# Rx_Universal_SK.net
KiCad netlist of a schematic drawn in Altium Designer
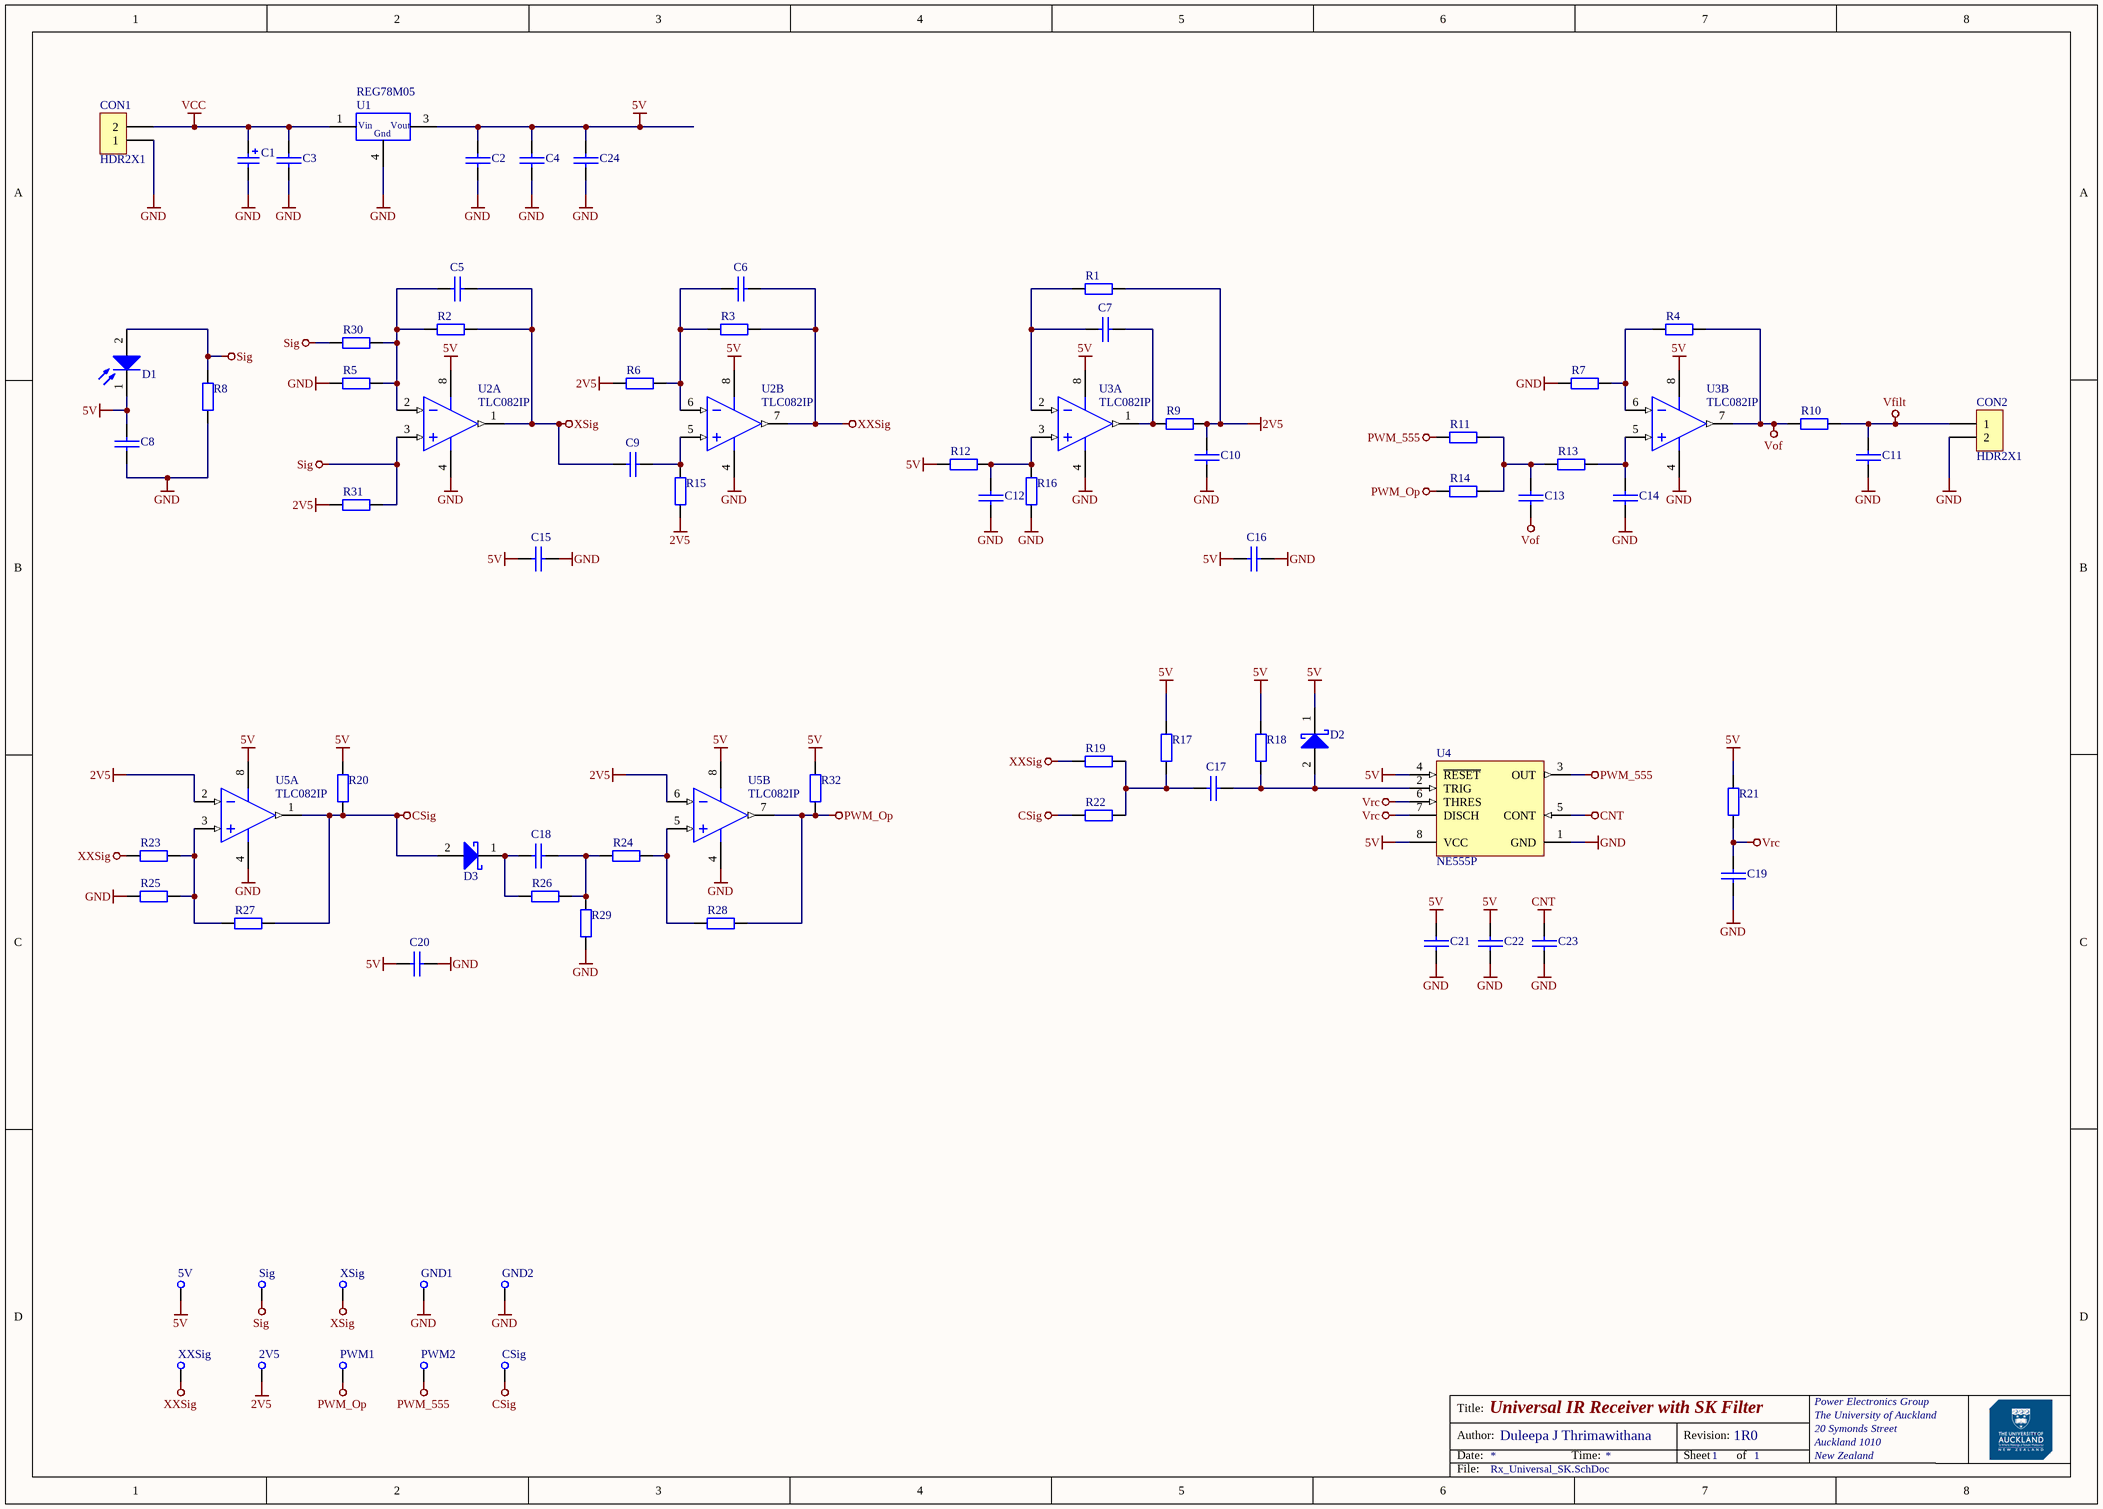
[diagram p0: Rx_Universal_SK.SchDoc]

(export (version "E")
  (design (tool "Eeschema 10.0.6"))
  (components
    (comp (ref "2V5")
      (value "TP TH")
      (footprint "TP_TH_2.5mm")
      (fields (field (name "SOURCE") "UoAPE_Connectors and Mechanical.SchLib"))
      (libsource (lib "ECSE@UoA") (part "TP TH"))
    )
    (comp (ref "5V")
      (value "TP TH")
      (footprint "TP_TH_2.5mm")
      (fields (field (name "SOURCE") "UoAPE_Connectors and Mechanical.SchLib"))
      (libsource (lib "ECSE@UoA") (part "TP TH"))
    )
    (comp (ref "C1") (value "ECAP") (footprint "CR05") (libsource (lib "ECSE@UoA") (part "ECAP")))
    (comp (ref "C2")
      (value "CCAP_TH_5P0")
      (footprint "CCAP_5P0")
      (description "TH ceramic cap with 5mm pitch")
      (libsource (lib "") (part "Symbol_2"))
    )
    (comp (ref "C3")
      (value "CCAP_TH_5P0")
      (footprint "CCAP_5P0")
      (description "TH ceramic cap with 5mm pitch")
      (libsource (lib "") (part "Symbol_2"))
    )
    (comp (ref "C4")
      (value "CCAP_TH_5P0")
      (footprint "CCAP_5P0")
      (description "TH ceramic cap with 5mm pitch")
      (libsource (lib "") (part "Symbol_2"))
    )
    (comp (ref "C5")
      (value "CCAP_TH_5P0")
      (footprint "CCAP_5P0")
      (description "TH ceramic cap with 5mm pitch")
      (libsource (lib "") (part "Symbol_2"))
    )
    (comp (ref "C6")
      (value "CCAP_TH_5P0")
      (footprint "CCAP_5P0")
      (description "TH ceramic cap with 5mm pitch")
      (libsource (lib "") (part "Symbol_2"))
    )
    (comp (ref "C7")
      (value "CCAP_TH_5P0")
      (footprint "CCAP_5P0")
      (description "TH ceramic cap with 5mm pitch")
      (libsource (lib "") (part "Symbol_2"))
    )
    (comp (ref "C8")
      (value "CCAP_TH_5P0")
      (footprint "CCAP_5P0")
      (description "TH ceramic cap with 5mm pitch")
      (libsource (lib "") (part "Symbol_2"))
    )
    (comp (ref "C9")
      (value "CCAP_TH_5P0")
      (footprint "CCAP_5P0")
      (description "TH ceramic cap with 5mm pitch")
      (libsource (lib "") (part "Symbol_2"))
    )
    (comp (ref "C10")
      (value "CCAP_TH_5P0")
      (footprint "CCAP_5P0")
      (description "TH ceramic cap with 5mm pitch")
      (libsource (lib "") (part "Symbol_2"))
    )
    (comp (ref "C11")
      (value "CCAP_TH_5P0")
      (footprint "CCAP_5P0")
      (description "TH ceramic cap with 5mm pitch")
      (libsource (lib "") (part "Symbol_2"))
    )
    (comp (ref "C12")
      (value "CCAP_TH_5P0")
      (footprint "CCAP_5P0")
      (description "TH ceramic cap with 5mm pitch")
      (libsource (lib "") (part "Symbol_2"))
    )
    (comp (ref "C13")
      (value "CCAP_TH_5P0")
      (footprint "CCAP_5P0")
      (description "TH ceramic cap with 5mm pitch")
      (libsource (lib "") (part "Symbol_2"))
    )
    (comp (ref "C14")
      (value "CCAP_TH_5P0")
      (footprint "CCAP_5P0")
      (description "TH ceramic cap with 5mm pitch")
      (libsource (lib "") (part "Symbol_2"))
    )
    (comp (ref "C15")
      (value "CCAP_TH_5P0")
      (footprint "CCAP_5P0")
      (description "TH ceramic cap with 5mm pitch")
      (libsource (lib "") (part "Symbol_2"))
    )
    (comp (ref "C16")
      (value "CCAP_TH_5P0")
      (footprint "CCAP_5P0")
      (description "TH ceramic cap with 5mm pitch")
      (libsource (lib "") (part "Symbol_2"))
    )
    (comp (ref "C17")
      (value "CCAP_TH_5P0")
      (footprint "CCAP_5P0")
      (description "TH ceramic cap with 5mm pitch")
      (libsource (lib "") (part "Symbol_2"))
    )
    (comp (ref "C18")
      (value "CCAP_TH_5P0")
      (footprint "CCAP_5P0")
      (description "TH ceramic cap with 5mm pitch")
      (libsource (lib "") (part "Symbol_2"))
    )
    (comp (ref "C19")
      (value "CCAP_TH_5P0")
      (footprint "CCAP_5P0")
      (description "TH ceramic cap with 5mm pitch")
      (libsource (lib "") (part "Symbol_2"))
    )
    (comp (ref "C20")
      (value "CCAP_TH_5P0")
      (footprint "CCAP_5P0")
      (description "TH ceramic cap with 5mm pitch")
      (libsource (lib "") (part "Symbol_2"))
    )
    (comp (ref "C21")
      (value "CCAP_TH_5P0")
      (footprint "CCAP_5P0")
      (description "TH ceramic cap with 5mm pitch")
      (libsource (lib "") (part "Symbol_2"))
    )
    (comp (ref "C22")
      (value "CCAP_TH_5P0")
      (footprint "CCAP_5P0")
      (description "TH ceramic cap with 5mm pitch")
      (libsource (lib "") (part "Symbol_2"))
    )
    (comp (ref "C23")
      (value "CCAP_TH_5P0")
      (footprint "CCAP_5P0")
      (description "TH ceramic cap with 5mm pitch")
      (libsource (lib "") (part "Symbol_2"))
    )
    (comp (ref "C24")
      (value "CCAP_TH_5P0")
      (footprint "CCAP_5P0")
      (description "TH ceramic cap with 5mm pitch")
      (libsource (lib "") (part "Symbol_2"))
    )
    (comp (ref "CON1")
      (value "HDR2X1")
      (footprint "HDR2X1_2P54")
      (description "Header 2X1")
      (libsource (lib "") (part "HDR2X1_1"))
    )
    (comp (ref "CON2")
      (value "HDR2X1")
      (footprint "HDR2X1_2P54")
      (description "Header 2X1")
      (libsource (lib "ECSE@UoA") (part "HDR2X1"))
    )
    (comp (ref "CSig")
      (value "TP TH")
      (footprint "TP_TH_2.5mm")
      (fields (field (name "SOURCE") "UoAPE_Connectors and Mechanical.SchLib"))
      (libsource (lib "ECSE@UoA") (part "TP TH"))
    )
    (comp (ref "D1")
      (value "PhotoD_TH")
      (footprint "TH_LED")
      (description "Photo diode")
      (libsource (lib "ECSE@UoA") (part "Copy of 8706943c75ba83719d021d2fdc84c58"))
    )
    (comp (ref "D2")
      (value "BAT85,113")
      (footprint "FP-SOD68-MFG")
      (description "Rectifier Diode, Schottky, 1 Phase, 1 Element, 0.2A, 30V V(RRM), Silicon, DO-34")
      (libsource (lib "ECSE@UoA") (part "1d6ec82d83fb6aee721767c19dac4b9"))
    )
    (comp (ref "D3")
      (value "BAT85,113")
      (footprint "FP-SOD68-MFG")
      (description "Rectifier Diode, Schottky, 1 Phase, 1 Element, 0.2A, 30V V(RRM), Silicon, DO-34")
      (libsource (lib "ECSE@UoA") (part "1d6ec82d83fb6aee721767c19dac4b9"))
    )
    (comp (ref "GND1")
      (value "TP TH")
      (footprint "TP_TH_2.5mm")
      (fields (field (name "SOURCE") "UoAPE_Connectors and Mechanical.SchLib"))
      (libsource (lib "ECSE@UoA") (part "TP TH"))
    )
    (comp (ref "GND2")
      (value "TP TH")
      (footprint "TP_TH_2.5mm")
      (fields (field (name "SOURCE") "UoAPE_Connectors and Mechanical.SchLib"))
      (libsource (lib "ECSE@UoA") (part "TP TH"))
    )
    (comp (ref "PWM1")
      (value "TP TH")
      (footprint "TP_TH_2.5mm")
      (fields (field (name "SOURCE") "UoAPE_Connectors and Mechanical.SchLib"))
      (libsource (lib "ECSE@UoA") (part "TP TH"))
    )
    (comp (ref "PWM2")
      (value "TP TH")
      (footprint "TP_TH_2.5mm")
      (fields (field (name "SOURCE") "UoAPE_Connectors and Mechanical.SchLib"))
      (libsource (lib "ECSE@UoA") (part "TP TH"))
    )
    (comp (ref "R1")
      (value "RESAX4")
      (footprint "RAX4")
      (description "Axial Resistor")
      (libsource (lib "") (part "Symbol_1"))
    )
    (comp (ref "R2")
      (value "RESAX4")
      (footprint "RAX4")
      (description "Axial Resistor")
      (libsource (lib "") (part "Symbol_1"))
    )
    (comp (ref "R3")
      (value "RESAX4")
      (footprint "RAX4")
      (description "Axial Resistor")
      (libsource (lib "") (part "Symbol_1"))
    )
    (comp (ref "R4")
      (value "RESAX4")
      (footprint "RAX4")
      (description "Axial Resistor")
      (libsource (lib "") (part "Symbol_1"))
    )
    (comp (ref "R5")
      (value "RESAX4")
      (footprint "RAX4")
      (description "Axial Resistor")
      (libsource (lib "") (part "Symbol_1"))
    )
    (comp (ref "R6")
      (value "RESAX4")
      (footprint "RAX4")
      (description "Axial Resistor")
      (libsource (lib "") (part "Symbol_1"))
    )
    (comp (ref "R7")
      (value "RESAX4")
      (footprint "RAX4")
      (description "Axial Resistor")
      (libsource (lib "") (part "Symbol_1"))
    )
    (comp (ref "R8")
      (value "RESAX4")
      (footprint "RAX4")
      (description "Axial Resistor")
      (libsource (lib "ECSE@UoA") (part "Symbol"))
    )
    (comp (ref "R9")
      (value "RESAX4")
      (footprint "RAX4")
      (description "Axial Resistor")
      (libsource (lib "") (part "Symbol_1"))
    )
    (comp (ref "R10")
      (value "RESAX4")
      (footprint "RAX4")
      (description "Axial Resistor")
      (libsource (lib "") (part "Symbol_1"))
    )
    (comp (ref "R11")
      (value "RESAX4")
      (footprint "RAX4")
      (description "Axial Resistor")
      (libsource (lib "") (part "Symbol_1"))
    )
    (comp (ref "R12")
      (value "RESAX4")
      (footprint "RAX4")
      (description "Axial Resistor")
      (libsource (lib "") (part "Symbol_1"))
    )
    (comp (ref "R13")
      (value "RESAX4")
      (footprint "RAX4")
      (description "Axial Resistor")
      (libsource (lib "") (part "Symbol_1"))
    )
    (comp (ref "R14")
      (value "RESAX4")
      (footprint "RAX4")
      (description "Axial Resistor")
      (libsource (lib "") (part "Symbol_1"))
    )
    (comp (ref "R15")
      (value "RESAX4")
      (footprint "RAX4")
      (description "Axial Resistor")
      (libsource (lib "ECSE@UoA") (part "Symbol"))
    )
    (comp (ref "R16")
      (value "RESAX4")
      (footprint "RAX4")
      (description "Axial Resistor")
      (libsource (lib "ECSE@UoA") (part "Symbol"))
    )
    (comp (ref "R17")
      (value "RESAX4")
      (footprint "RAX4")
      (description "Axial Resistor")
      (libsource (lib "ECSE@UoA") (part "Symbol"))
    )
    (comp (ref "R18")
      (value "RESAX4")
      (footprint "RAX4")
      (description "Axial Resistor")
      (libsource (lib "ECSE@UoA") (part "Symbol"))
    )
    (comp (ref "R19")
      (value "RESAX4")
      (footprint "RAX4")
      (description "Axial Resistor")
      (libsource (lib "") (part "Symbol_1"))
    )
    (comp (ref "R20")
      (value "RESAX4")
      (footprint "RAX4")
      (description "Axial Resistor")
      (libsource (lib "") (part "Symbol_3"))
    )
    (comp (ref "R21")
      (value "RESAX4")
      (footprint "RAX4")
      (description "Axial Resistor")
      (libsource (lib "ECSE@UoA") (part "Symbol"))
    )
    (comp (ref "R22")
      (value "RESAX4")
      (footprint "RAX4")
      (description "Axial Resistor")
      (libsource (lib "") (part "Symbol_1"))
    )
    (comp (ref "R23")
      (value "RESAX4")
      (footprint "RAX4")
      (description "Axial Resistor")
      (libsource (lib "") (part "Symbol_1"))
    )
    (comp (ref "R24")
      (value "RESAX4")
      (footprint "RAX4")
      (description "Axial Resistor")
      (libsource (lib "") (part "Symbol_1"))
    )
    (comp (ref "R25")
      (value "RESAX4")
      (footprint "RAX4")
      (description "Axial Resistor")
      (libsource (lib "") (part "Symbol_1"))
    )
    (comp (ref "R26")
      (value "RESAX4")
      (footprint "RAX4")
      (description "Axial Resistor")
      (libsource (lib "") (part "Symbol_1"))
    )
    (comp (ref "R27")
      (value "RESAX4")
      (footprint "RAX4")
      (description "Axial Resistor")
      (libsource (lib "") (part "Symbol_1"))
    )
    (comp (ref "R28")
      (value "RESAX4")
      (footprint "RAX4")
      (description "Axial Resistor")
      (libsource (lib "") (part "Symbol_1"))
    )
    (comp (ref "R29")
      (value "RESAX4")
      (footprint "RAX4")
      (description "Axial Resistor")
      (libsource (lib "") (part "Symbol_3"))
    )
    (comp (ref "R30")
      (value "RESAX4")
      (footprint "RAX4")
      (description "Axial Resistor")
      (libsource (lib "") (part "Symbol_1"))
    )
    (comp (ref "R31")
      (value "RESAX4")
      (footprint "RAX4")
      (description "Axial Resistor")
      (libsource (lib "") (part "Symbol_1"))
    )
    (comp (ref "R32")
      (value "RESAX4")
      (footprint "RAX4")
      (description "Axial Resistor")
      (libsource (lib "") (part "Symbol_3"))
    )
    (comp (ref "Sig")
      (value "TP TH")
      (footprint "TP_TH_2.5mm")
      (fields (field (name "SOURCE") "UoAPE_Connectors and Mechanical.SchLib"))
      (libsource (lib "ECSE@UoA") (part "TP TH"))
    )
    (comp (ref "U1")
      (value "REG78M05")
      (footprint "TO220_Reg")
      (description "78M Series Linear Regulators")
      (libsource (lib "ECSE@UoA") (part "REG78MXX"))
    )
    (comp (ref "U2")
      (value "TLC082IP")
      (footprint "P0008A")
      (description "Operational Amplifier, 2 Func, 3000uV Offset-Max, BIMOS, PDIP8")
      (fields (field (name "POWER") "100mW"))
      (libsource (lib "ECSE@UoA") (part "TI-TLV_TLC-8"))
    )
    (comp (ref "U3")
      (value "TLC082IP")
      (footprint "P0008A")
      (description "Operational Amplifier, 2 Func, 3000uV Offset-Max, BIMOS, PDIP8")
      (fields (field (name "POWER") "100mW"))
      (libsource (lib "ECSE@UoA") (part "TI-TLV_TLC-8"))
    )
    (comp (ref "U4")
      (value "NE555P")
      (footprint "P0008A")
      (description "1 Func, BIPolar, PDIP8")
      (libsource (lib "ECSE@UoA") (part "TI-NE555-P8"))
    )
    (comp (ref "U5")
      (value "TLC082IP")
      (footprint "P0008A")
      (description "Operational Amplifier, 2 Func, 3000uV Offset-Max, BIMOS, PDIP8")
      (fields (field (name "POWER") "100mW"))
      (libsource (lib "ECSE@UoA") (part "TI-TLV_TLC-8"))
    )
    (comp (ref "XSig")
      (value "TP TH")
      (footprint "TP_TH_2.5mm")
      (fields (field (name "SOURCE") "UoAPE_Connectors and Mechanical.SchLib"))
      (libsource (lib "ECSE@UoA") (part "TP TH"))
    )
    (comp (ref "XXSig")
      (value "TP TH")
      (footprint "TP_TH_2.5mm")
      (fields (field (name "SOURCE") "UoAPE_Connectors and Mechanical.SchLib"))
      (libsource (lib "ECSE@UoA") (part "TP TH"))
    )
  )
  (nets
    (net (code "1") (name "2V5") (class "Default")
      (node (ref "2V5") (pin "1") (pinfunction "1_1") (pintype "passive"))
      (node (ref "C10") (pin "1") (pinfunction "1_1") (pintype "passive"))
      (node (ref "R1") (pin "1") (pinfunction "1_1") (pintype "passive"))
      (node (ref "R15") (pin "1") (pinfunction "1_1") (pintype "passive"))
      (node (ref "R31") (pin "2") (pinfunction "2_2") (pintype "passive"))
      (node (ref "R6") (pin "2") (pinfunction "2_2") (pintype "passive"))
      (node (ref "R9") (pin "1") (pinfunction "1_1") (pintype "passive"))
      (node (ref "U5") (pin "2") (pinfunction "IN1-_2") (pintype "input"))
      (node (ref "U5") (pin "6") (pinfunction "IN2-_6") (pintype "input"))
    )
    (net (code "2") (name "5V") (class "Default")
      (node (ref "5V") (pin "1") (pinfunction "1_1") (pintype "passive"))
      (node (ref "C15") (pin "2") (pinfunction "2_2") (pintype "passive"))
      (node (ref "C16") (pin "2") (pinfunction "2_2") (pintype "passive"))
      (node (ref "C2") (pin "2") (pinfunction "2_2") (pintype "passive"))
      (node (ref "C20") (pin "2") (pinfunction "2_2") (pintype "passive"))
      (node (ref "C21") (pin "2") (pinfunction "2_2") (pintype "passive"))
      (node (ref "C22") (pin "2") (pinfunction "2_2") (pintype "passive"))
      (node (ref "C24") (pin "2") (pinfunction "2_2") (pintype "passive"))
      (node (ref "C4") (pin "2") (pinfunction "2_2") (pintype "passive"))
      (node (ref "C8") (pin "2") (pinfunction "2_2") (pintype "passive"))
      (node (ref "D1") (pin "1") (pinfunction "C_1") (pintype "passive"))
      (node (ref "D2") (pin "1") (pinfunction "C_1") (pintype "passive"))
      (node (ref "R12") (pin "2") (pinfunction "2_2") (pintype "passive"))
      (node (ref "R17") (pin "2") (pinfunction "2_2") (pintype "passive"))
      (node (ref "R18") (pin "2") (pinfunction "2_2") (pintype "passive"))
      (node (ref "R20") (pin "1") (pinfunction "1_1") (pintype "passive"))
      (node (ref "R21") (pin "2") (pinfunction "2_2") (pintype "passive"))
      (node (ref "R32") (pin "1") (pinfunction "1_1") (pintype "passive"))
      (node (ref "U1") (pin "3") (pinfunction "Vout_3") (pintype "passive"))
      (node (ref "U2") (pin "8") (pinfunction "VDD_8") (pintype "power_in"))
      (node (ref "U3") (pin "8") (pinfunction "VDD_8") (pintype "power_in"))
      (node (ref "U4") (pin "4") (pinfunction "~{RESET}_4") (pintype "input"))
      (node (ref "U4") (pin "8") (pinfunction "VCC_8") (pintype "power_in"))
      (node (ref "U5") (pin "8") (pinfunction "VDD_8") (pintype "power_in"))
    )
    (net (code "3") (name "CNT") (class "Default")
      (node (ref "C23") (pin "2") (pinfunction "2_2") (pintype "passive"))
      (node (ref "U4") (pin "5") (pinfunction "CONT_5") (pintype "input"))
    )
    (net (code "4") (name "CSig") (class "Default")
      (node (ref "CSig") (pin "1") (pinfunction "1_1") (pintype "passive"))
      (node (ref "D3") (pin "2") (pinfunction "A_2") (pintype "passive"))
      (node (ref "R20") (pin "2") (pinfunction "2_2") (pintype "passive"))
      (node (ref "R22") (pin "2") (pinfunction "2_2") (pintype "passive"))
      (node (ref "R27") (pin "1") (pinfunction "1_1") (pintype "passive"))
      (node (ref "U5") (pin "1") (pinfunction "OUT1_1") (pintype "output"))
    )
    (net (code "5") (name "GND") (class "Default")
      (node (ref "C1") (pin "2") (pinfunction "2_2") (pintype "passive"))
      (node (ref "C10") (pin "2") (pinfunction "2_2") (pintype "passive"))
      (node (ref "C11") (pin "1") (pinfunction "1_1") (pintype "passive"))
      (node (ref "C12") (pin "2") (pinfunction "2_2") (pintype "passive"))
      (node (ref "C14") (pin "2") (pinfunction "2_2") (pintype "passive"))
      (node (ref "C15") (pin "1") (pinfunction "1_1") (pintype "passive"))
      (node (ref "C16") (pin "1") (pinfunction "1_1") (pintype "passive"))
      (node (ref "C19") (pin "1") (pinfunction "1_1") (pintype "passive"))
      (node (ref "C2") (pin "1") (pinfunction "1_1") (pintype "passive"))
      (node (ref "C20") (pin "1") (pinfunction "1_1") (pintype "passive"))
      (node (ref "C21") (pin "1") (pinfunction "1_1") (pintype "passive"))
      (node (ref "C22") (pin "1") (pinfunction "1_1") (pintype "passive"))
      (node (ref "C23") (pin "1") (pinfunction "1_1") (pintype "passive"))
      (node (ref "C24") (pin "1") (pinfunction "1_1") (pintype "passive"))
      (node (ref "C3") (pin "1") (pinfunction "1_1") (pintype "passive"))
      (node (ref "C4") (pin "1") (pinfunction "1_1") (pintype "passive"))
      (node (ref "C8") (pin "1") (pinfunction "1_1") (pintype "passive"))
      (node (ref "CON1") (pin "1") (pinfunction "1_1") (pintype "passive"))
      (node (ref "CON2") (pin "2") (pinfunction "2_2") (pintype "passive"))
      (node (ref "GND1") (pin "1") (pinfunction "1_1") (pintype "passive"))
      (node (ref "GND2") (pin "1") (pinfunction "1_1") (pintype "passive"))
      (node (ref "R16") (pin "1") (pinfunction "1_1") (pintype "passive"))
      (node (ref "R25") (pin "2") (pinfunction "2_2") (pintype "passive"))
      (node (ref "R29") (pin "2") (pinfunction "2_2") (pintype "passive"))
      (node (ref "R5") (pin "2") (pinfunction "2_2") (pintype "passive"))
      (node (ref "R7") (pin "2") (pinfunction "2_2") (pintype "passive"))
      (node (ref "R8") (pin "1") (pinfunction "1_1") (pintype "passive"))
      (node (ref "U1") (pin "4") (pinfunction "Gnd_4") (pintype "passive"))
      (node (ref "U2") (pin "4") (pinfunction "GND_4") (pintype "power_in"))
      (node (ref "U3") (pin "4") (pinfunction "GND_4") (pintype "power_in"))
      (node (ref "U4") (pin "1") (pinfunction "GND_1") (pintype "power_in"))
      (node (ref "U5") (pin "4") (pinfunction "GND_4") (pintype "power_in"))
    )
    (net (code "6") (name "Net-(C13-Pad2)") (class "Default")
      (node (ref "C13") (pin "2") (pinfunction "2_2") (pintype "passive"))
      (node (ref "R11") (pin "1") (pinfunction "1_1") (pintype "passive"))
      (node (ref "R13") (pin "2") (pinfunction "2_2") (pintype "passive"))
      (node (ref "R14") (pin "1") (pinfunction "1_1") (pintype "passive"))
    )
    (net (code "7") (name "Net-(C17-Pad2)") (class "Default")
      (node (ref "C17") (pin "2") (pinfunction "2_2") (pintype "passive"))
      (node (ref "R17") (pin "1") (pinfunction "1_1") (pintype "passive"))
      (node (ref "R19") (pin "1") (pinfunction "1_1") (pintype "passive"))
      (node (ref "R22") (pin "1") (pinfunction "1_1") (pintype "passive"))
    )
    (net (code "8") (name "Net-(C18-Pad1)") (class "Default")
      (node (ref "C18") (pin "1") (pinfunction "1_1") (pintype "passive"))
      (node (ref "R24") (pin "2") (pinfunction "2_2") (pintype "passive"))
      (node (ref "R26") (pin "1") (pinfunction "1_1") (pintype "passive"))
      (node (ref "R29") (pin "1") (pinfunction "1_1") (pintype "passive"))
    )
    (net (code "9") (name "Net-(D2-A)") (class "Default")
      (node (ref "C17") (pin "1") (pinfunction "1_1") (pintype "passive"))
      (node (ref "D2") (pin "2") (pinfunction "A_2") (pintype "passive"))
      (node (ref "R18") (pin "1") (pinfunction "1_1") (pintype "passive"))
      (node (ref "U4") (pin "2") (pinfunction "TRIG_2") (pintype "input"))
    )
    (net (code "10") (name "Net-(D3-C)") (class "Default")
      (node (ref "C18") (pin "2") (pinfunction "2_2") (pintype "passive"))
      (node (ref "D3") (pin "1") (pinfunction "C_1") (pintype "passive"))
      (node (ref "R26") (pin "2") (pinfunction "2_2") (pintype "passive"))
    )
    (net (code "11") (name "Net-(U2A-IN1-)") (class "Default")
      (node (ref "C5") (pin "2") (pinfunction "2_2") (pintype "passive"))
      (node (ref "R2") (pin "2") (pinfunction "2_2") (pintype "passive"))
      (node (ref "R30") (pin "1") (pinfunction "1_1") (pintype "passive"))
      (node (ref "R5") (pin "1") (pinfunction "1_1") (pintype "passive"))
      (node (ref "U2") (pin "2") (pinfunction "IN1-_2") (pintype "input"))
    )
    (net (code "12") (name "Net-(U2B-IN2+)") (class "Default")
      (node (ref "C9") (pin "1") (pinfunction "1_1") (pintype "passive"))
      (node (ref "R15") (pin "2") (pinfunction "2_2") (pintype "passive"))
      (node (ref "U2") (pin "5") (pinfunction "IN2+_5") (pintype "input"))
    )
    (net (code "13") (name "Net-(U2B-IN2-)") (class "Default")
      (node (ref "C6") (pin "2") (pinfunction "2_2") (pintype "passive"))
      (node (ref "R3") (pin "2") (pinfunction "2_2") (pintype "passive"))
      (node (ref "R6") (pin "1") (pinfunction "1_1") (pintype "passive"))
      (node (ref "U2") (pin "6") (pinfunction "IN2-_6") (pintype "input"))
    )
    (net (code "14") (name "Net-(U3A-IN1+)") (class "Default")
      (node (ref "C12") (pin "1") (pinfunction "1_1") (pintype "passive"))
      (node (ref "R12") (pin "1") (pinfunction "1_1") (pintype "passive"))
      (node (ref "R16") (pin "2") (pinfunction "2_2") (pintype "passive"))
      (node (ref "U3") (pin "3") (pinfunction "IN1+_3") (pintype "input"))
    )
    (net (code "15") (name "Net-(U3A-IN1-)") (class "Default")
      (node (ref "C7") (pin "2") (pinfunction "2_2") (pintype "passive"))
      (node (ref "R1") (pin "2") (pinfunction "2_2") (pintype "passive"))
      (node (ref "U3") (pin "2") (pinfunction "IN1-_2") (pintype "input"))
    )
    (net (code "16") (name "Net-(U3A-OUT1)") (class "Default")
      (node (ref "C7") (pin "1") (pinfunction "1_1") (pintype "passive"))
      (node (ref "R9") (pin "2") (pinfunction "2_2") (pintype "passive"))
      (node (ref "U3") (pin "1") (pinfunction "OUT1_1") (pintype "output"))
    )
    (net (code "17") (name "Net-(U3B-IN2+)") (class "Default")
      (node (ref "C14") (pin "1") (pinfunction "1_1") (pintype "passive"))
      (node (ref "R13") (pin "1") (pinfunction "1_1") (pintype "passive"))
      (node (ref "U3") (pin "5") (pinfunction "IN2+_5") (pintype "input"))
    )
    (net (code "18") (name "Net-(U3B-IN2-)") (class "Default")
      (node (ref "R4") (pin "2") (pinfunction "2_2") (pintype "passive"))
      (node (ref "R7") (pin "1") (pinfunction "1_1") (pintype "passive"))
      (node (ref "U3") (pin "6") (pinfunction "IN2-_6") (pintype "input"))
    )
    (net (code "19") (name "Net-(U5A-IN1+)") (class "Default")
      (node (ref "R23") (pin "1") (pinfunction "1_1") (pintype "passive"))
      (node (ref "R25") (pin "1") (pinfunction "1_1") (pintype "passive"))
      (node (ref "R27") (pin "2") (pinfunction "2_2") (pintype "passive"))
      (node (ref "U5") (pin "3") (pinfunction "IN1+_3") (pintype "input"))
    )
    (net (code "20") (name "Net-(U5B-IN2+)") (class "Default")
      (node (ref "R24") (pin "1") (pinfunction "1_1") (pintype "passive"))
      (node (ref "R28") (pin "2") (pinfunction "2_2") (pintype "passive"))
      (node (ref "U5") (pin "5") (pinfunction "IN2+_5") (pintype "input"))
    )
    (net (code "21") (name "PWM_555") (class "Default")
      (node (ref "PWM2") (pin "1") (pinfunction "1_1") (pintype "passive"))
      (node (ref "R11") (pin "2") (pinfunction "2_2") (pintype "passive"))
      (node (ref "U4") (pin "3") (pinfunction "OUT_3") (pintype "output"))
    )
    (net (code "22") (name "PWM_Op") (class "Default")
      (node (ref "PWM1") (pin "1") (pinfunction "1_1") (pintype "passive"))
      (node (ref "R14") (pin "2") (pinfunction "2_2") (pintype "passive"))
      (node (ref "R28") (pin "1") (pinfunction "1_1") (pintype "passive"))
      (node (ref "R32") (pin "2") (pinfunction "2_2") (pintype "passive"))
      (node (ref "U5") (pin "7") (pinfunction "OUT2_7") (pintype "output"))
    )
    (net (code "23") (name "Sig") (class "Default")
      (node (ref "D1") (pin "2") (pinfunction "A_2") (pintype "passive"))
      (node (ref "R30") (pin "2") (pinfunction "2_2") (pintype "passive"))
      (node (ref "R31") (pin "1") (pinfunction "1_1") (pintype "passive"))
      (node (ref "R8") (pin "2") (pinfunction "2_2") (pintype "passive"))
      (node (ref "Sig") (pin "1") (pinfunction "1_1") (pintype "passive"))
      (node (ref "U2") (pin "3") (pinfunction "IN1+_3") (pintype "input"))
    )
    (net (code "24") (name "VCC") (class "Default")
      (node (ref "C1") (pin "1") (pinfunction "1_1") (pintype "passive"))
      (node (ref "C3") (pin "2") (pinfunction "2_2") (pintype "passive"))
      (node (ref "CON1") (pin "2") (pinfunction "2_2") (pintype "passive"))
      (node (ref "U1") (pin "1") (pinfunction "Vin_1") (pintype "passive"))
    )
    (net (code "25") (name "Vfilt") (class "Default")
      (node (ref "C11") (pin "2") (pinfunction "2_2") (pintype "passive"))
      (node (ref "CON2") (pin "1") (pinfunction "1_1") (pintype "passive"))
      (node (ref "R10") (pin "1") (pinfunction "1_1") (pintype "passive"))
    )
    (net (code "26") (name "Vof") (class "Default")
      (node (ref "C13") (pin "1") (pinfunction "1_1") (pintype "passive"))
      (node (ref "R10") (pin "2") (pinfunction "2_2") (pintype "passive"))
      (node (ref "R4") (pin "1") (pinfunction "1_1") (pintype "passive"))
      (node (ref "U3") (pin "7") (pinfunction "OUT2_7") (pintype "output"))
    )
    (net (code "27") (name "Vrc") (class "Default")
      (node (ref "C19") (pin "2") (pinfunction "2_2") (pintype "passive"))
      (node (ref "R21") (pin "1") (pinfunction "1_1") (pintype "passive"))
      (node (ref "U4") (pin "6") (pinfunction "THRES_6") (pintype "input"))
      (node (ref "U4") (pin "7") (pinfunction "DISCH_7") (pintype "open_collector"))
    )
    (net (code "28") (name "XSig") (class "Default")
      (node (ref "C5") (pin "1") (pinfunction "1_1") (pintype "passive"))
      (node (ref "C9") (pin "2") (pinfunction "2_2") (pintype "passive"))
      (node (ref "R2") (pin "1") (pinfunction "1_1") (pintype "passive"))
      (node (ref "U2") (pin "1") (pinfunction "OUT1_1") (pintype "output"))
      (node (ref "XSig") (pin "1") (pinfunction "1_1") (pintype "passive"))
    )
    (net (code "29") (name "XXSig") (class "Default")
      (node (ref "C6") (pin "1") (pinfunction "1_1") (pintype "passive"))
      (node (ref "R19") (pin "2") (pinfunction "2_2") (pintype "passive"))
      (node (ref "R23") (pin "2") (pinfunction "2_2") (pintype "passive"))
      (node (ref "R3") (pin "1") (pinfunction "1_1") (pintype "passive"))
      (node (ref "U2") (pin "7") (pinfunction "OUT2_7") (pintype "output"))
      (node (ref "XXSig") (pin "1") (pinfunction "1_1") (pintype "passive"))
    )
  )
)
